# EVB-ANNA-B5_SCHEM_0006_PinHeaders_ULED.net
KiCad netlist of a schematic drawn in Altium Designer
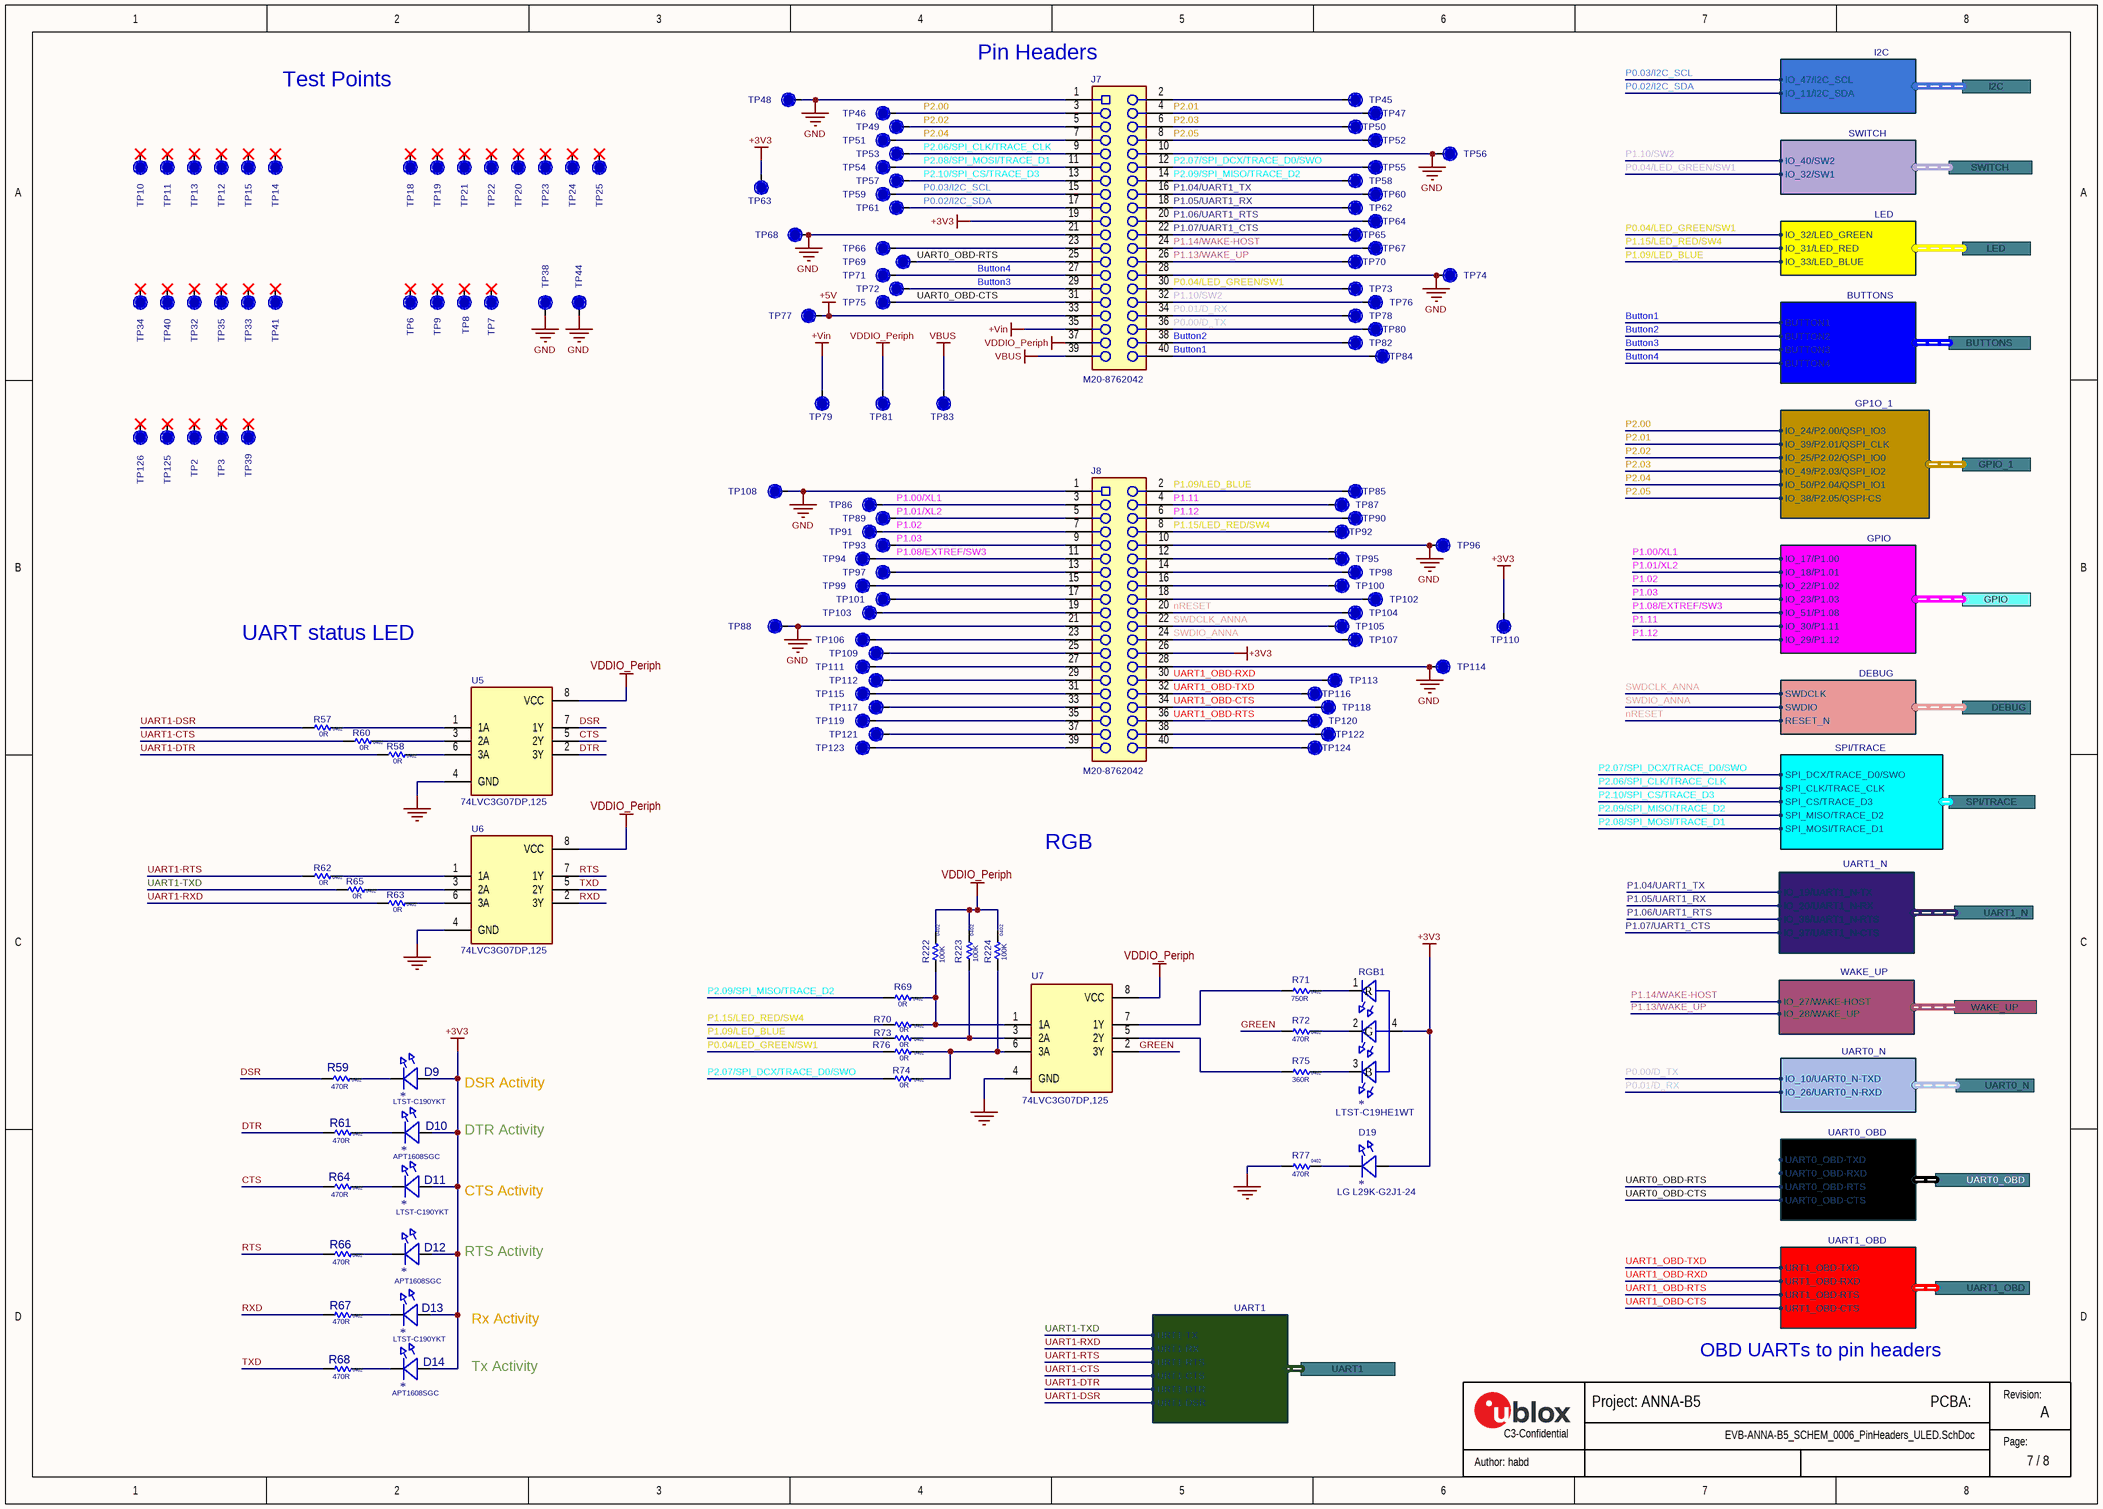
[diagram p0: EVB-ANNA-B5_SCHEM_0006_PinHeaders_ULED.SchDoc]

(export (version "E")
  (design (tool "Eeschema 10.0.6"))
  (components
    (comp (ref "D9")
      (value "UBXH11-0000057")
      (footprint "LED_0603_YELLOW")
      (description "DIODE LED SMT YELLOW CLEAR LENS 2.1V 10MA 0603 YELLOW")
      (fields
        (field (name "COLOR") "*")
        (field (name "MANUFACTURER") "Lite-on Technology Corporation")
        (field (name "MANUFACTURER P/N") "LTST-C190YKT")
        (field (name "EDITOR") "eric.moog")
      )
      (libsource (lib "UBX_Parts_DB_Lib") (part "LED_BASE"))
    )
    (comp (ref "D10")
      (value "UBXH11-0000001")
      (footprint "LED_0603_GREEN")
      (description "LED SMD 0603 GREEN 2.5V 20mA")
      (fields
        (field (name "COLOR") "*")
        (field (name "MANUFACTURER") "Kingbright")
        (field (name "MANUFACTURER P/N") "APT1608SGC")
        (field (name "EDITOR") "gianni.falleroni")
        (field (name "RELEASED BY") "alex.claville")
      )
      (libsource (lib "UBX_Parts_DB_Lib") (part "LED_BASE"))
    )
    (comp (ref "D11")
      (value "UBXH11-0000057")
      (footprint "LED_0603_YELLOW")
      (description "DIODE LED SMT YELLOW CLEAR LENS 2.1V 10MA 0603 YELLOW")
      (fields
        (field (name "COLOR") "*")
        (field (name "MANUFACTURER") "Lite-on Technology Corporation")
        (field (name "MANUFACTURER P/N") "LTST-C190YKT")
        (field (name "EDITOR") "eric.moog")
      )
      (libsource (lib "UBX_Parts_DB_Lib") (part "LED_BASE"))
    )
    (comp (ref "D12")
      (value "UBXH11-0000001")
      (footprint "LED_0603_GREEN")
      (description "LED SMD 0603 GREEN 2.5V 20mA")
      (fields
        (field (name "COLOR") "*")
        (field (name "MANUFACTURER") "Kingbright")
        (field (name "MANUFACTURER P/N") "APT1608SGC")
        (field (name "EDITOR") "gianni.falleroni")
        (field (name "RELEASED BY") "alex.claville")
      )
      (libsource (lib "UBX_Parts_DB_Lib") (part "LED_BASE"))
    )
    (comp (ref "D13")
      (value "UBXH11-0000057")
      (footprint "LED_0603_YELLOW")
      (description "DIODE LED SMT YELLOW CLEAR LENS 2.1V 10MA 0603 YELLOW")
      (fields
        (field (name "COLOR") "*")
        (field (name "MANUFACTURER") "Lite-on Technology Corporation")
        (field (name "MANUFACTURER P/N") "LTST-C190YKT")
        (field (name "EDITOR") "eric.moog")
      )
      (libsource (lib "UBX_Parts_DB_Lib") (part "LED_BASE"))
    )
    (comp (ref "D14")
      (value "UBXH11-0000001")
      (footprint "LED_0603_GREEN")
      (description "LED SMD 0603 GREEN 2.5V 20mA")
      (fields
        (field (name "COLOR") "*")
        (field (name "MANUFACTURER") "Kingbright")
        (field (name "MANUFACTURER P/N") "APT1608SGC")
        (field (name "EDITOR") "gianni.falleroni")
        (field (name "RELEASED BY") "alex.claville")
      )
      (libsource (lib "UBX_Parts_DB_Lib") (part "LED_BASE"))
    )
    (comp (ref "D19")
      (value "UBXH11-0000018")
      (footprint "LED_0603_1600Lx800Wx400H_600x800Pad_800G_FLX")
      (description "LED CHIP 0603 LOW CURRENT OSRAM 0.002A GREEN 2.2V 2mA")
      (fields
        (field (name "COLOR") "*")
        (field (name "MANUFACTURER") "Osram")
        (field (name "MANUFACTURER P/N") "LG L29K-G2J1-24")
        (field (name "EDITOR") "johann.furrer")
        (field (name "RELEASED BY") "martin.grasse")
      )
      (libsource (lib "UBX_Parts_DB_Lib") (part "LED_BASE"))
    )
    (comp (ref "J7")
      (value "~")
      (footprint "M208762042")
      (description "Connector")
      (fields
        (field (name "MANUFACTURER_PART_NUMBER") "M20-8762042")
        (field (name "MOUSER PART NUMBER") "855-M20-8762042")
      )
      (libsource (lib "SamacSys") (part "M20-8762042"))
    )
    (comp (ref "J8")
      (value "~")
      (footprint "M208762042")
      (description "Connector")
      (fields
        (field (name "MANUFACTURER_PART_NUMBER") "M20-8762042")
        (field (name "MOUSER PART NUMBER") "855-M20-8762042")
      )
      (libsource (lib "SamacSys") (part "M20-8762042"))
    )
    (comp (ref "R57")
      (value "0R")
      (footprint "RES 0402 HD")
      (description "RES THICK FILM CHIP 0402 0R 0 100mW")
      (fields
        (field (name "SIZE") "0402")
        (field (name "PART NUMBER") "UBXH18-0003002")
        (field (name "TOLERANCE") "0")
        (field (name "EDITOR") "charlotte.biber")
        (field (name "RELEASED BY") "peter.mueller")
      )
      (libsource (lib "UBX_Parts_DB_Lib") (part "Res sm"))
    )
    (comp (ref "R58")
      (value "0R")
      (footprint "RES 0402 HD")
      (description "RES THICK FILM CHIP 0402 0R 0 100mW")
      (fields
        (field (name "SIZE") "0402")
        (field (name "PART NUMBER") "UBXH18-0003002")
        (field (name "TOLERANCE") "0")
        (field (name "EDITOR") "charlotte.biber")
        (field (name "RELEASED BY") "peter.mueller")
      )
      (libsource (lib "UBX_Parts_DB_Lib") (part "Res sm"))
    )
    (comp (ref "R59")
      (value "470R")
      (footprint "RES_0402_1100Lx600Wx400H_500x600Pad_400G_FLX")
      (description "RES THICK FILM CHIP 0402 470R 5% 100mW")
      (fields
        (field (name "SIZE") "0402")
        (field (name "PART NUMBER") "UBXH18-0008041")
        (field (name "TOLERANCE") "5%")
        (field (name "EDITOR") "roland.rust")
        (field (name "RELEASED BY") "roland.rust")
      )
      (libsource (lib "UBX_Parts_DB_Lib") (part "Res sm"))
    )
    (comp (ref "R60")
      (value "0R")
      (footprint "RES 0402 HD")
      (description "RES THICK FILM CHIP 0402 0R 0 100mW")
      (fields
        (field (name "SIZE") "0402")
        (field (name "PART NUMBER") "UBXH18-0003002")
        (field (name "TOLERANCE") "0")
        (field (name "EDITOR") "charlotte.biber")
        (field (name "RELEASED BY") "peter.mueller")
      )
      (libsource (lib "UBX_Parts_DB_Lib") (part "Res sm"))
    )
    (comp (ref "R61")
      (value "470R")
      (footprint "RES_0402_1100Lx600Wx400H_500x600Pad_400G_FLX")
      (description "RES THICK FILM CHIP 0402 470R 5% 100mW")
      (fields
        (field (name "SIZE") "0402")
        (field (name "PART NUMBER") "UBXH18-0008041")
        (field (name "TOLERANCE") "5%")
        (field (name "EDITOR") "roland.rust")
        (field (name "RELEASED BY") "roland.rust")
      )
      (libsource (lib "UBX_Parts_DB_Lib") (part "Res sm"))
    )
    (comp (ref "R62")
      (value "0R")
      (footprint "RES 0402 HD")
      (description "RES THICK FILM CHIP 0402 0R 0 100mW")
      (fields
        (field (name "SIZE") "0402")
        (field (name "PART NUMBER") "UBXH18-0003002")
        (field (name "TOLERANCE") "0")
        (field (name "EDITOR") "charlotte.biber")
        (field (name "RELEASED BY") "peter.mueller")
      )
      (libsource (lib "UBX_Parts_DB_Lib") (part "Res sm"))
    )
    (comp (ref "R63")
      (value "0R")
      (footprint "RES 0402 HD")
      (description "RES THICK FILM CHIP 0402 0R 0 100mW")
      (fields
        (field (name "SIZE") "0402")
        (field (name "PART NUMBER") "UBXH18-0003002")
        (field (name "TOLERANCE") "0")
        (field (name "EDITOR") "charlotte.biber")
        (field (name "RELEASED BY") "peter.mueller")
      )
      (libsource (lib "UBX_Parts_DB_Lib") (part "Res sm"))
    )
    (comp (ref "R64")
      (value "470R")
      (footprint "RES_0402_1100Lx600Wx400H_500x600Pad_400G_FLX")
      (description "RES THICK FILM CHIP 0402 470R 5% 100mW")
      (fields
        (field (name "SIZE") "0402")
        (field (name "PART NUMBER") "UBXH18-0008041")
        (field (name "TOLERANCE") "5%")
        (field (name "EDITOR") "roland.rust")
        (field (name "RELEASED BY") "roland.rust")
      )
      (libsource (lib "UBX_Parts_DB_Lib") (part "Res sm"))
    )
    (comp (ref "R65")
      (value "0R")
      (footprint "RES 0402 HD")
      (description "RES THICK FILM CHIP 0402 0R 0 100mW")
      (fields
        (field (name "SIZE") "0402")
        (field (name "PART NUMBER") "UBXH18-0003002")
        (field (name "TOLERANCE") "0")
        (field (name "EDITOR") "charlotte.biber")
        (field (name "RELEASED BY") "peter.mueller")
      )
      (libsource (lib "UBX_Parts_DB_Lib") (part "Res sm"))
    )
    (comp (ref "R66")
      (value "470R")
      (footprint "RES_0402_1100Lx600Wx400H_500x600Pad_400G_FLX")
      (description "RES THICK FILM CHIP 0402 470R 5% 100mW")
      (fields
        (field (name "SIZE") "0402")
        (field (name "PART NUMBER") "UBXH18-0008041")
        (field (name "TOLERANCE") "5%")
        (field (name "EDITOR") "roland.rust")
        (field (name "RELEASED BY") "roland.rust")
      )
      (libsource (lib "UBX_Parts_DB_Lib") (part "Res sm"))
    )
    (comp (ref "R67")
      (value "470R")
      (footprint "RES_0402_1100Lx600Wx400H_500x600Pad_400G_FLX")
      (description "RES THICK FILM CHIP 0402 470R 5% 100mW")
      (fields
        (field (name "SIZE") "0402")
        (field (name "PART NUMBER") "UBXH18-0008041")
        (field (name "TOLERANCE") "5%")
        (field (name "EDITOR") "roland.rust")
        (field (name "RELEASED BY") "roland.rust")
      )
      (libsource (lib "UBX_Parts_DB_Lib") (part "Res sm"))
    )
    (comp (ref "R68")
      (value "470R")
      (footprint "RES_0402_1100Lx600Wx400H_500x600Pad_400G_FLX")
      (description "RES THICK FILM CHIP 0402 470R 5% 100mW")
      (fields
        (field (name "SIZE") "0402")
        (field (name "PART NUMBER") "UBXH18-0008041")
        (field (name "TOLERANCE") "5%")
        (field (name "EDITOR") "roland.rust")
        (field (name "RELEASED BY") "roland.rust")
      )
      (libsource (lib "UBX_Parts_DB_Lib") (part "Res sm"))
    )
    (comp (ref "R69")
      (value "0R")
      (footprint "RES 0402 HD")
      (description "RES THICK FILM CHIP 0402 0R 0 100mW")
      (fields
        (field (name "SIZE") "0402")
        (field (name "PART NUMBER") "UBXH18-0003002")
        (field (name "TOLERANCE") "0")
        (field (name "EDITOR") "charlotte.biber")
        (field (name "RELEASED BY") "peter.mueller")
      )
      (libsource (lib "UBX_Parts_DB_Lib") (part "Res sm"))
    )
    (comp (ref "R70")
      (value "0R")
      (footprint "RES 0402 HD")
      (description "RES THICK FILM CHIP 0402 0R 0 100mW")
      (fields
        (field (name "SIZE") "0402")
        (field (name "PART NUMBER") "UBXH18-0003002")
        (field (name "TOLERANCE") "0")
        (field (name "EDITOR") "charlotte.biber")
        (field (name "RELEASED BY") "peter.mueller")
      )
      (libsource (lib "UBX_Parts_DB_Lib") (part "Res sm"))
    )
    (comp (ref "R71")
      (value "750R")
      (footprint "RES_0402_1100Lx600Wx400H_500x600Pad_400G_FLX")
      (description "RES THICK FILM CHIP 0402 750R 5% 100mW")
      (fields
        (field (name "SIZE") "0402")
        (field (name "PART NUMBER") "UBXH18-0008046")
        (field (name "TOLERANCE") "5%")
        (field (name "EDITOR") "jaka.bevk")
        (field (name "RELEASED BY") "erian.bezhani")
      )
      (libsource (lib "UBX_Parts_DB_Lib") (part "Res sm"))
    )
    (comp (ref "R72")
      (value "470R")
      (footprint "RES_0402_1100Lx600Wx400H_500x600Pad_400G_FLX")
      (description "RES THICK FILM CHIP 0402 470R 5% 100mW")
      (fields
        (field (name "SIZE") "0402")
        (field (name "PART NUMBER") "UBXH18-0008041")
        (field (name "TOLERANCE") "5%")
        (field (name "EDITOR") "roland.rust")
        (field (name "RELEASED BY") "roland.rust")
      )
      (libsource (lib "UBX_Parts_DB_Lib") (part "Res sm"))
    )
    (comp (ref "R73")
      (value "0R")
      (footprint "RES 0402 HD")
      (description "RES THICK FILM CHIP 0402 0R 0 100mW")
      (fields
        (field (name "SIZE") "0402")
        (field (name "PART NUMBER") "UBXH18-0003002")
        (field (name "TOLERANCE") "0")
        (field (name "EDITOR") "charlotte.biber")
        (field (name "RELEASED BY") "peter.mueller")
      )
      (libsource (lib "UBX_Parts_DB_Lib") (part "Res sm"))
    )
    (comp (ref "R74")
      (value "0R")
      (footprint "RES 0402 HD")
      (description "RES THICK FILM CHIP 0402 0R 0 100mW")
      (fields
        (field (name "SIZE") "0402")
        (field (name "PART NUMBER") "UBXH18-0003002")
        (field (name "TOLERANCE") "0")
        (field (name "EDITOR") "charlotte.biber")
        (field (name "RELEASED BY") "peter.mueller")
      )
      (libsource (lib "UBX_Parts_DB_Lib") (part "Res sm"))
    )
    (comp (ref "R75")
      (value "360R")
      (footprint "RES_0402_1100Lx600Wx400H_500x600Pad_400G_FLX")
      (description "RES THICK FILM CHIP 0402 360R 1% 63mW")
      (fields
        (field (name "SIZE") "0402")
        (field (name "PART NUMBER") "UBXH18-0000216")
        (field (name "TOLERANCE") "1%")
        (field (name "EDITOR") "michael.hein")
        (field (name "RELEASED BY") "vasyl.dykyy")
      )
      (libsource (lib "UBX_Parts_DB_Lib") (part "Res sm"))
    )
    (comp (ref "R76")
      (value "0R")
      (footprint "RES 0402 HD")
      (description "RES THICK FILM CHIP 0402 0R 0 100mW")
      (fields
        (field (name "SIZE") "0402")
        (field (name "PART NUMBER") "UBXH18-0003002")
        (field (name "TOLERANCE") "0")
        (field (name "EDITOR") "charlotte.biber")
        (field (name "RELEASED BY") "peter.mueller")
      )
      (libsource (lib "UBX_Parts_DB_Lib") (part "Res sm"))
    )
    (comp (ref "R77")
      (value "470R")
      (footprint "RES_0402_1100Lx600Wx400H_500x600Pad_400G_FLX")
      (description "RES THICK FILM CHIP 0402 470R 5% 100mW")
      (fields
        (field (name "SIZE") "0402")
        (field (name "PART NUMBER") "UBXH18-0008041")
        (field (name "TOLERANCE") "5%")
        (field (name "EDITOR") "roland.rust")
        (field (name "RELEASED BY") "roland.rust")
      )
      (libsource (lib "UBX_Parts_DB_Lib") (part "Res sm"))
    )
    (comp (ref "R222")
      (value "100K")
      (footprint "RES 0402 HD")
      (description "RES THICK FILM CHIP 0402 100K 1% 63mW")
      (fields
        (field (name "SIZE") "0402")
        (field (name "PART NUMBER") "UBXH18-0000005")
        (field (name "TOLERANCE") "1%")
        (field (name "EDITOR") "dario.antonaz")
        (field (name "RELEASED BY") "sandro.sestan")
      )
      (libsource (lib "UBX_Parts_DB_Lib") (part "Res sm"))
    )
    (comp (ref "R223")
      (value "100K")
      (footprint "RES 0402 HD")
      (description "RES THICK FILM CHIP 0402 100K 1% 63mW")
      (fields
        (field (name "SIZE") "0402")
        (field (name "PART NUMBER") "UBXH18-0000005")
        (field (name "TOLERANCE") "1%")
        (field (name "EDITOR") "dario.antonaz")
        (field (name "RELEASED BY") "sandro.sestan")
      )
      (libsource (lib "UBX_Parts_DB_Lib") (part "Res sm"))
    )
    (comp (ref "R224")
      (value "100K")
      (footprint "RES 0402 HD")
      (description "RES THICK FILM CHIP 0402 100K 1% 63mW")
      (fields
        (field (name "SIZE") "0402")
        (field (name "PART NUMBER") "UBXH18-0000005")
        (field (name "TOLERANCE") "1%")
        (field (name "EDITOR") "dario.antonaz")
        (field (name "RELEASED BY") "sandro.sestan")
      )
      (libsource (lib "UBX_Parts_DB_Lib") (part "Res sm"))
    )
    (comp (ref "RGB1")
      (value "115-00026")
      (footprint "LED_1616")
      (description "LED RGB SMT 0606")
      (fields
        (field (name "COLOR") "*")
        (field (name "MANUFACTURER PART NUMBER 1") "LTST-C19HE1WT")
        (field (name "VOLTAGE") "None")
      )
      (libsource (lib "Arena_Parts_DB_Lib") (part "LED_RGB_CA_4"))
    )
    (comp (ref "TP2")
      (value "TP10R")
      (footprint "TP10R")
      (description "Testpoint, Round 1.0mm Dia")
      (fields (field (name "ADDED BY") "Jeremy D") (field (name "CHECKED BY") "Paul B"))
      (libsource (lib "LEGACY_Rigado_AltiumLib") (part "TP_R"))
    )
    (comp (ref "TP3")
      (value "TP10R")
      (footprint "TP10R")
      (description "Testpoint, Round 1.0mm Dia")
      (fields (field (name "ADDED BY") "Jeremy D") (field (name "CHECKED BY") "Paul B"))
      (libsource (lib "LEGACY_Rigado_AltiumLib") (part "TP_R"))
    )
    (comp (ref "TP6")
      (value "TP10R")
      (footprint "TP10R")
      (description "Testpoint, Round 1.0mm Dia")
      (fields (field (name "ADDED BY") "Jeremy D") (field (name "CHECKED BY") "Paul B"))
      (libsource (lib "") (part "TP_R_1"))
    )
    (comp (ref "TP7")
      (value "TP10R")
      (footprint "TP10R")
      (description "Testpoint, Round 1.0mm Dia")
      (fields (field (name "ADDED BY") "Jeremy D") (field (name "CHECKED BY") "Paul B"))
      (libsource (lib "LEGACY_Rigado_AltiumLib") (part "TP_R"))
    )
    (comp (ref "TP8")
      (value "TP10R")
      (footprint "TP10R")
      (description "Testpoint, Round 1.0mm Dia")
      (fields (field (name "ADDED BY") "Jeremy D") (field (name "CHECKED BY") "Paul B"))
      (libsource (lib "LEGACY_Rigado_AltiumLib") (part "TP_R"))
    )
    (comp (ref "TP9")
      (value "TP10R")
      (footprint "TP10R")
      (description "Testpoint, Round 1.0mm Dia")
      (fields (field (name "ADDED BY") "Jeremy D") (field (name "CHECKED BY") "Paul B"))
      (libsource (lib "LEGACY_Rigado_AltiumLib") (part "TP_R"))
    )
    (comp (ref "TP10")
      (value "TP10R")
      (footprint "TP10R")
      (description "Testpoint, Round 1.0mm Dia")
      (fields (field (name "ADDED BY") "Jeremy D") (field (name "CHECKED BY") "Paul B"))
      (libsource (lib "LEGACY_Rigado_AltiumLib") (part "TP_R"))
    )
    (comp (ref "TP11")
      (value "TP10R")
      (footprint "TP10R")
      (description "Testpoint, Round 1.0mm Dia")
      (fields (field (name "ADDED BY") "Jeremy D") (field (name "CHECKED BY") "Paul B"))
      (libsource (lib "LEGACY_Rigado_AltiumLib") (part "TP_R"))
    )
    (comp (ref "TP12")
      (value "TP10R")
      (footprint "TP10R")
      (description "Testpoint, Round 1.0mm Dia")
      (fields (field (name "ADDED BY") "Jeremy D") (field (name "CHECKED BY") "Paul B"))
      (libsource (lib "LEGACY_Rigado_AltiumLib") (part "TP_R"))
    )
    (comp (ref "TP13")
      (value "TP10R")
      (footprint "TP10R")
      (description "Testpoint, Round 1.0mm Dia")
      (fields (field (name "ADDED BY") "Jeremy D") (field (name "CHECKED BY") "Paul B"))
      (libsource (lib "LEGACY_Rigado_AltiumLib") (part "TP_R"))
    )
    (comp (ref "TP14")
      (value "TP10R")
      (footprint "TP10R")
      (description "Testpoint, Round 1.0mm Dia")
      (fields (field (name "ADDED BY") "Jeremy D") (field (name "CHECKED BY") "Paul B"))
      (libsource (lib "LEGACY_Rigado_AltiumLib") (part "TP_R"))
    )
    (comp (ref "TP15")
      (value "TP10R")
      (footprint "TP10R")
      (description "Testpoint, Round 1.0mm Dia")
      (fields (field (name "ADDED BY") "Jeremy D") (field (name "CHECKED BY") "Paul B"))
      (libsource (lib "LEGACY_Rigado_AltiumLib") (part "TP_R"))
    )
    (comp (ref "TP18")
      (value "TP10R")
      (footprint "TP10R")
      (description "Testpoint, Round 1.0mm Dia")
      (fields (field (name "ADDED BY") "Jeremy D") (field (name "CHECKED BY") "Paul B"))
      (libsource (lib "LEGACY_Rigado_AltiumLib") (part "TP_R"))
    )
    (comp (ref "TP19")
      (value "TP10R")
      (footprint "TP10R")
      (description "Testpoint, Round 1.0mm Dia")
      (fields (field (name "ADDED BY") "Jeremy D") (field (name "CHECKED BY") "Paul B"))
      (libsource (lib "LEGACY_Rigado_AltiumLib") (part "TP_R"))
    )
    (comp (ref "TP20")
      (value "TP10R")
      (footprint "TP10R")
      (description "Testpoint, Round 1.0mm Dia")
      (fields (field (name "ADDED BY") "Jeremy D") (field (name "CHECKED BY") "Paul B"))
      (libsource (lib "LEGACY_Rigado_AltiumLib") (part "TP_R"))
    )
    (comp (ref "TP21")
      (value "TP10R")
      (footprint "TP10R")
      (description "Testpoint, Round 1.0mm Dia")
      (fields (field (name "ADDED BY") "Jeremy D") (field (name "CHECKED BY") "Paul B"))
      (libsource (lib "LEGACY_Rigado_AltiumLib") (part "TP_R"))
    )
    (comp (ref "TP22")
      (value "TP10R")
      (footprint "TP10R")
      (description "Testpoint, Round 1.0mm Dia")
      (fields (field (name "ADDED BY") "Jeremy D") (field (name "CHECKED BY") "Paul B"))
      (libsource (lib "LEGACY_Rigado_AltiumLib") (part "TP_R"))
    )
    (comp (ref "TP23")
      (value "TP10R")
      (footprint "TP10R")
      (description "Testpoint, Round 1.0mm Dia")
      (fields (field (name "ADDED BY") "Jeremy D") (field (name "CHECKED BY") "Paul B"))
      (libsource (lib "LEGACY_Rigado_AltiumLib") (part "TP_R"))
    )
    (comp (ref "TP24")
      (value "TP10R")
      (footprint "TP10R")
      (description "Testpoint, Round 1.0mm Dia")
      (fields (field (name "ADDED BY") "Jeremy D") (field (name "CHECKED BY") "Paul B"))
      (libsource (lib "LEGACY_Rigado_AltiumLib") (part "TP_R"))
    )
    (comp (ref "TP25")
      (value "TP10R")
      (footprint "TP10R")
      (description "Testpoint, Round 1.0mm Dia")
      (fields (field (name "ADDED BY") "Jeremy D") (field (name "CHECKED BY") "Paul B"))
      (libsource (lib "LEGACY_Rigado_AltiumLib") (part "TP_R"))
    )
    (comp (ref "TP32")
      (value "TP10R")
      (footprint "TP10R")
      (description "Testpoint, Round 1.0mm Dia")
      (fields (field (name "ADDED BY") "Jeremy D") (field (name "CHECKED BY") "Paul B"))
      (libsource (lib "LEGACY_Rigado_AltiumLib") (part "TP_R"))
    )
    (comp (ref "TP33")
      (value "TP10R")
      (footprint "TP10R")
      (description "Testpoint, Round 1.0mm Dia")
      (fields (field (name "ADDED BY") "Jeremy D") (field (name "CHECKED BY") "Paul B"))
      (libsource (lib "LEGACY_Rigado_AltiumLib") (part "TP_R"))
    )
    (comp (ref "TP34")
      (value "TP10R")
      (footprint "TP10R")
      (description "Testpoint, Round 1.0mm Dia")
      (fields (field (name "ADDED BY") "Jeremy D") (field (name "CHECKED BY") "Paul B"))
      (libsource (lib "LEGACY_Rigado_AltiumLib") (part "TP_R"))
    )
    (comp (ref "TP35")
      (value "TP10R")
      (footprint "TP10R")
      (description "Testpoint, Round 1.0mm Dia")
      (fields (field (name "ADDED BY") "Jeremy D") (field (name "CHECKED BY") "Paul B"))
      (libsource (lib "LEGACY_Rigado_AltiumLib") (part "TP_R"))
    )
    (comp (ref "TP38")
      (value "TP10R")
      (footprint "TP10R")
      (description "Testpoint, Round 1.0mm Dia")
      (fields (field (name "ADDED BY") "Jeremy D") (field (name "CHECKED BY") "Paul B"))
      (libsource (lib "LEGACY_Rigado_AltiumLib") (part "TP_R"))
    )
    (comp (ref "TP39")
      (value "TP10R")
      (footprint "TP10R")
      (description "Testpoint, Round 1.0mm Dia")
      (fields (field (name "ADDED BY") "Jeremy D") (field (name "CHECKED BY") "Paul B"))
      (libsource (lib "LEGACY_Rigado_AltiumLib") (part "TP_R"))
    )
    (comp (ref "TP40")
      (value "TP10R")
      (footprint "TP10R")
      (description "Testpoint, Round 1.0mm Dia")
      (fields (field (name "ADDED BY") "Jeremy D") (field (name "CHECKED BY") "Paul B"))
      (libsource (lib "LEGACY_Rigado_AltiumLib") (part "TP_R"))
    )
    (comp (ref "TP41")
      (value "TP10R")
      (footprint "TP10R")
      (description "Testpoint, Round 1.0mm Dia")
      (fields (field (name "ADDED BY") "Jeremy D") (field (name "CHECKED BY") "Paul B"))
      (libsource (lib "LEGACY_Rigado_AltiumLib") (part "TP_R"))
    )
    (comp (ref "TP44")
      (value "TP10R")
      (footprint "TP10R")
      (description "Testpoint, Round 1.0mm Dia")
      (fields (field (name "ADDED BY") "Jeremy D") (field (name "CHECKED BY") "Paul B"))
      (libsource (lib "LEGACY_Rigado_AltiumLib") (part "TP_R"))
    )
    (comp (ref "TP45")
      (value "TP10R")
      (footprint "TP10R")
      (description "Testpoint, Round 1.0mm Dia")
      (fields (field (name "ADDED BY") "Jeremy D") (field (name "CHECKED BY") "Paul B"))
      (libsource (lib "LEGACY_Rigado_AltiumLib") (part "TP_R"))
    )
    (comp (ref "TP46")
      (value "TP10R")
      (footprint "TP10R")
      (description "Testpoint, Round 1.0mm Dia")
      (fields (field (name "ADDED BY") "Jeremy D") (field (name "CHECKED BY") "Paul B"))
      (libsource (lib "LEGACY_Rigado_AltiumLib") (part "TP_R"))
    )
    (comp (ref "TP47")
      (value "TP10R")
      (footprint "TP10R")
      (description "Testpoint, Round 1.0mm Dia")
      (fields (field (name "ADDED BY") "Jeremy D") (field (name "CHECKED BY") "Paul B"))
      (libsource (lib "") (part "TP_R_1"))
    )
    (comp (ref "TP48")
      (value "TP10R")
      (footprint "TP10R")
      (description "Testpoint, Round 1.0mm Dia")
      (fields (field (name "ADDED BY") "Jeremy D") (field (name "CHECKED BY") "Paul B"))
      (libsource (lib "LEGACY_Rigado_AltiumLib") (part "TP_R"))
    )
    (comp (ref "TP49")
      (value "TP10R")
      (footprint "TP10R")
      (description "Testpoint, Round 1.0mm Dia")
      (fields (field (name "ADDED BY") "Jeremy D") (field (name "CHECKED BY") "Paul B"))
      (libsource (lib "LEGACY_Rigado_AltiumLib") (part "TP_R"))
    )
    (comp (ref "TP50")
      (value "TP10R")
      (footprint "TP10R")
      (description "Testpoint, Round 1.0mm Dia")
      (fields (field (name "ADDED BY") "Jeremy D") (field (name "CHECKED BY") "Paul B"))
      (libsource (lib "") (part "TP_R_1"))
    )
    (comp (ref "TP51")
      (value "TP10R")
      (footprint "TP10R")
      (description "Testpoint, Round 1.0mm Dia")
      (fields (field (name "ADDED BY") "Jeremy D") (field (name "CHECKED BY") "Paul B"))
      (libsource (lib "LEGACY_Rigado_AltiumLib") (part "TP_R"))
    )
    (comp (ref "TP52")
      (value "TP10R")
      (footprint "TP10R")
      (description "Testpoint, Round 1.0mm Dia")
      (fields (field (name "ADDED BY") "Jeremy D") (field (name "CHECKED BY") "Paul B"))
      (libsource (lib "LEGACY_Rigado_AltiumLib") (part "TP_R"))
    )
    (comp (ref "TP53")
      (value "TP10R")
      (footprint "TP10R")
      (description "Testpoint, Round 1.0mm Dia")
      (fields (field (name "ADDED BY") "Jeremy D") (field (name "CHECKED BY") "Paul B"))
      (libsource (lib "LEGACY_Rigado_AltiumLib") (part "TP_R"))
    )
    (comp (ref "TP54")
      (value "TP10R")
      (footprint "TP10R")
      (description "Testpoint, Round 1.0mm Dia")
      (fields (field (name "ADDED BY") "Jeremy D") (field (name "CHECKED BY") "Paul B"))
      (libsource (lib "LEGACY_Rigado_AltiumLib") (part "TP_R"))
    )
    (comp (ref "TP55")
      (value "TP10R")
      (footprint "TP10R")
      (description "Testpoint, Round 1.0mm Dia")
      (fields (field (name "ADDED BY") "Jeremy D") (field (name "CHECKED BY") "Paul B"))
      (libsource (lib "LEGACY_Rigado_AltiumLib") (part "TP_R"))
    )
    (comp (ref "TP56")
      (value "TP10R")
      (footprint "TP10R")
      (description "Testpoint, Round 1.0mm Dia")
      (fields (field (name "ADDED BY") "Jeremy D") (field (name "CHECKED BY") "Paul B"))
      (libsource (lib "LEGACY_Rigado_AltiumLib") (part "TP_R"))
    )
    (comp (ref "TP57")
      (value "TP10R")
      (footprint "TP10R")
      (description "Testpoint, Round 1.0mm Dia")
      (fields (field (name "ADDED BY") "Jeremy D") (field (name "CHECKED BY") "Paul B"))
      (libsource (lib "LEGACY_Rigado_AltiumLib") (part "TP_R"))
    )
    (comp (ref "TP58")
      (value "TP10R")
      (footprint "TP10R")
      (description "Testpoint, Round 1.0mm Dia")
      (fields (field (name "ADDED BY") "Jeremy D") (field (name "CHECKED BY") "Paul B"))
      (libsource (lib "LEGACY_Rigado_AltiumLib") (part "TP_R"))
    )
    (comp (ref "TP59")
      (value "TP10R")
      (footprint "TP10R")
      (description "Testpoint, Round 1.0mm Dia")
      (fields (field (name "ADDED BY") "Jeremy D") (field (name "CHECKED BY") "Paul B"))
      (libsource (lib "LEGACY_Rigado_AltiumLib") (part "TP_R"))
    )
    (comp (ref "TP60")
      (value "TP10R")
      (footprint "TP10R")
      (description "Testpoint, Round 1.0mm Dia")
      (fields (field (name "ADDED BY") "Jeremy D") (field (name "CHECKED BY") "Paul B"))
      (libsource (lib "LEGACY_Rigado_AltiumLib") (part "TP_R"))
    )
    (comp (ref "TP61")
      (value "TP10R")
      (footprint "TP10R")
      (description "Testpoint, Round 1.0mm Dia")
      (fields (field (name "ADDED BY") "Jeremy D") (field (name "CHECKED BY") "Paul B"))
      (libsource (lib "LEGACY_Rigado_AltiumLib") (part "TP_R"))
    )
    (comp (ref "TP62")
      (value "TP10R")
      (footprint "TP10R")
      (description "Testpoint, Round 1.0mm Dia")
      (fields (field (name "ADDED BY") "Jeremy D") (field (name "CHECKED BY") "Paul B"))
      (libsource (lib "LEGACY_Rigado_AltiumLib") (part "TP_R"))
    )
    (comp (ref "TP63")
      (value "TP10R")
      (footprint "TP10R")
      (description "Testpoint, Round 1.0mm Dia")
      (fields (field (name "ADDED BY") "Jeremy D") (field (name "CHECKED BY") "Paul B"))
      (libsource (lib "LEGACY_Rigado_AltiumLib") (part "TP_R"))
    )
    (comp (ref "TP64")
      (value "TP10R")
      (footprint "TP10R")
      (description "Testpoint, Round 1.0mm Dia")
      (fields (field (name "ADDED BY") "Jeremy D") (field (name "CHECKED BY") "Paul B"))
      (libsource (lib "") (part "TP_R_1"))
    )
    (comp (ref "TP65")
      (value "TP10R")
      (footprint "TP10R")
      (description "Testpoint, Round 1.0mm Dia")
      (fields (field (name "ADDED BY") "Jeremy D") (field (name "CHECKED BY") "Paul B"))
      (libsource (lib "") (part "TP_R_1"))
    )
    (comp (ref "TP66")
      (value "TP10R")
      (footprint "TP10R")
      (description "Testpoint, Round 1.0mm Dia")
      (fields (field (name "ADDED BY") "Jeremy D") (field (name "CHECKED BY") "Paul B"))
      (libsource (lib "LEGACY_Rigado_AltiumLib") (part "TP_R"))
    )
    (comp (ref "TP67")
      (value "TP10R")
      (footprint "TP10R")
      (description "Testpoint, Round 1.0mm Dia")
      (fields (field (name "ADDED BY") "Jeremy D") (field (name "CHECKED BY") "Paul B"))
      (libsource (lib "") (part "TP_R_1"))
    )
    (comp (ref "TP68")
      (value "TP10R")
      (footprint "TP10R")
      (description "Testpoint, Round 1.0mm Dia")
      (fields (field (name "ADDED BY") "Jeremy D") (field (name "CHECKED BY") "Paul B"))
      (libsource (lib "LEGACY_Rigado_AltiumLib") (part "TP_R"))
    )
    (comp (ref "TP69")
      (value "TP10R")
      (footprint "TP10R")
      (description "Testpoint, Round 1.0mm Dia")
      (fields (field (name "ADDED BY") "Jeremy D") (field (name "CHECKED BY") "Paul B"))
      (libsource (lib "LEGACY_Rigado_AltiumLib") (part "TP_R"))
    )
    (comp (ref "TP70")
      (value "TP10R")
      (footprint "TP10R")
      (description "Testpoint, Round 1.0mm Dia")
      (fields (field (name "ADDED BY") "Jeremy D") (field (name "CHECKED BY") "Paul B"))
      (libsource (lib "LEGACY_Rigado_AltiumLib") (part "TP_R"))
    )
    (comp (ref "TP71")
      (value "TP10R")
      (footprint "TP10R")
      (description "Testpoint, Round 1.0mm Dia")
      (fields (field (name "ADDED BY") "Jeremy D") (field (name "CHECKED BY") "Paul B"))
      (libsource (lib "LEGACY_Rigado_AltiumLib") (part "TP_R"))
    )
    (comp (ref "TP72")
      (value "TP10R")
      (footprint "TP10R")
      (description "Testpoint, Round 1.0mm Dia")
      (fields (field (name "ADDED BY") "Jeremy D") (field (name "CHECKED BY") "Paul B"))
      (libsource (lib "LEGACY_Rigado_AltiumLib") (part "TP_R"))
    )
    (comp (ref "TP73")
      (value "TP10R")
      (footprint "TP10R")
      (description "Testpoint, Round 1.0mm Dia")
      (fields (field (name "ADDED BY") "Jeremy D") (field (name "CHECKED BY") "Paul B"))
      (libsource (lib "") (part "TP_R_1"))
    )
    (comp (ref "TP74")
      (value "TP10R")
      (footprint "TP10R")
      (description "Testpoint, Round 1.0mm Dia")
      (fields (field (name "ADDED BY") "Jeremy D") (field (name "CHECKED BY") "Paul B"))
      (libsource (lib "") (part "TP_R_1"))
    )
    (comp (ref "TP75")
      (value "TP10R")
      (footprint "TP10R")
      (description "Testpoint, Round 1.0mm Dia")
      (fields (field (name "ADDED BY") "Jeremy D") (field (name "CHECKED BY") "Paul B"))
      (libsource (lib "LEGACY_Rigado_AltiumLib") (part "TP_R"))
    )
    (comp (ref "TP76")
      (value "TP10R")
      (footprint "TP10R")
      (description "Testpoint, Round 1.0mm Dia")
      (fields (field (name "ADDED BY") "Jeremy D") (field (name "CHECKED BY") "Paul B"))
      (libsource (lib "") (part "TP_R_1"))
    )
    (comp (ref "TP77")
      (value "TP10R")
      (footprint "TP10R")
      (description "Testpoint, Round 1.0mm Dia")
      (fields (field (name "ADDED BY") "Jeremy D") (field (name "CHECKED BY") "Paul B"))
      (libsource (lib "LEGACY_Rigado_AltiumLib") (part "TP_R"))
    )
    (comp (ref "TP78")
      (value "TP10R")
      (footprint "TP10R")
      (description "Testpoint, Round 1.0mm Dia")
      (fields (field (name "ADDED BY") "Jeremy D") (field (name "CHECKED BY") "Paul B"))
      (libsource (lib "") (part "TP_R_1"))
    )
    (comp (ref "TP79")
      (value "TP10R")
      (footprint "TP10R")
      (description "Testpoint, Round 1.0mm Dia")
      (fields (field (name "ADDED BY") "Jeremy D") (field (name "CHECKED BY") "Paul B"))
      (libsource (lib "LEGACY_Rigado_AltiumLib") (part "TP_R"))
    )
    (comp (ref "TP80")
      (value "TP10R")
      (footprint "TP10R")
      (description "Testpoint, Round 1.0mm Dia")
      (fields (field (name "ADDED BY") "Jeremy D") (field (name "CHECKED BY") "Paul B"))
      (libsource (lib "") (part "TP_R_1"))
    )
    (comp (ref "TP81")
      (value "TP10R")
      (footprint "TP10R")
      (description "Testpoint, Round 1.0mm Dia")
      (fields (field (name "ADDED BY") "Jeremy D") (field (name "CHECKED BY") "Paul B"))
      (libsource (lib "LEGACY_Rigado_AltiumLib") (part "TP_R"))
    )
    (comp (ref "TP82")
      (value "TP10R")
      (footprint "TP10R")
      (description "Testpoint, Round 1.0mm Dia")
      (fields (field (name "ADDED BY") "Jeremy D") (field (name "CHECKED BY") "Paul B"))
      (libsource (lib "") (part "TP_R_1"))
    )
    (comp (ref "TP83")
      (value "TP10R")
      (footprint "TP10R")
      (description "Testpoint, Round 1.0mm Dia")
      (fields (field (name "ADDED BY") "Jeremy D") (field (name "CHECKED BY") "Paul B"))
      (libsource (lib "LEGACY_Rigado_AltiumLib") (part "TP_R"))
    )
    (comp (ref "TP84")
      (value "TP10R")
      (footprint "TP10R")
      (description "Testpoint, Round 1.0mm Dia")
      (fields (field (name "ADDED BY") "Jeremy D") (field (name "CHECKED BY") "Paul B"))
      (libsource (lib "") (part "TP_R_1"))
    )
    (comp (ref "TP85")
      (value "TP10R")
      (footprint "TP10R")
      (description "Testpoint, Round 1.0mm Dia")
      (fields (field (name "ADDED BY") "Jeremy D") (field (name "CHECKED BY") "Paul B"))
      (libsource (lib "") (part "TP_R_1"))
    )
    (comp (ref "TP86")
      (value "TP10R")
      (footprint "TP10R")
      (description "Testpoint, Round 1.0mm Dia")
      (fields (field (name "ADDED BY") "Jeremy D") (field (name "CHECKED BY") "Paul B"))
      (libsource (lib "LEGACY_Rigado_AltiumLib") (part "TP_R"))
    )
    (comp (ref "TP87")
      (value "TP10R")
      (footprint "TP10R")
      (description "Testpoint, Round 1.0mm Dia")
      (fields (field (name "ADDED BY") "Jeremy D") (field (name "CHECKED BY") "Paul B"))
      (libsource (lib "") (part "TP_R_1"))
    )
    (comp (ref "TP88")
      (value "TP10R")
      (footprint "TP10R")
      (description "Testpoint, Round 1.0mm Dia")
      (fields (field (name "ADDED BY") "Jeremy D") (field (name "CHECKED BY") "Paul B"))
      (libsource (lib "LEGACY_Rigado_AltiumLib") (part "TP_R"))
    )
    (comp (ref "TP89")
      (value "TP10R")
      (footprint "TP10R")
      (description "Testpoint, Round 1.0mm Dia")
      (fields (field (name "ADDED BY") "Jeremy D") (field (name "CHECKED BY") "Paul B"))
      (libsource (lib "LEGACY_Rigado_AltiumLib") (part "TP_R"))
    )
    (comp (ref "TP90")
      (value "TP10R")
      (footprint "TP10R")
      (description "Testpoint, Round 1.0mm Dia")
      (fields (field (name "ADDED BY") "Jeremy D") (field (name "CHECKED BY") "Paul B"))
      (libsource (lib "") (part "TP_R_1"))
    )
    (comp (ref "TP91")
      (value "TP10R")
      (footprint "TP10R")
      (description "Testpoint, Round 1.0mm Dia")
      (fields (field (name "ADDED BY") "Jeremy D") (field (name "CHECKED BY") "Paul B"))
      (libsource (lib "LEGACY_Rigado_AltiumLib") (part "TP_R"))
    )
    (comp (ref "TP92")
      (value "TP10R")
      (footprint "TP10R")
      (description "Testpoint, Round 1.0mm Dia")
      (fields (field (name "ADDED BY") "Jeremy D") (field (name "CHECKED BY") "Paul B"))
      (libsource (lib "LEGACY_Rigado_AltiumLib") (part "TP_R"))
    )
    (comp (ref "TP93")
      (value "TP10R")
      (footprint "TP10R")
      (description "Testpoint, Round 1.0mm Dia")
      (fields (field (name "ADDED BY") "Jeremy D") (field (name "CHECKED BY") "Paul B"))
      (libsource (lib "LEGACY_Rigado_AltiumLib") (part "TP_R"))
    )
    (comp (ref "TP94")
      (value "TP10R")
      (footprint "TP10R")
      (description "Testpoint, Round 1.0mm Dia")
      (fields (field (name "ADDED BY") "Jeremy D") (field (name "CHECKED BY") "Paul B"))
      (libsource (lib "LEGACY_Rigado_AltiumLib") (part "TP_R"))
    )
    (comp (ref "TP95")
      (value "TP10R")
      (footprint "TP10R")
      (description "Testpoint, Round 1.0mm Dia")
      (fields (field (name "ADDED BY") "Jeremy D") (field (name "CHECKED BY") "Paul B"))
      (libsource (lib "LEGACY_Rigado_AltiumLib") (part "TP_R"))
    )
    (comp (ref "TP96")
      (value "TP10R")
      (footprint "TP10R")
      (description "Testpoint, Round 1.0mm Dia")
      (fields (field (name "ADDED BY") "Jeremy D") (field (name "CHECKED BY") "Paul B"))
      (libsource (lib "") (part "TP_R_1"))
    )
    (comp (ref "TP97")
      (value "TP10R")
      (footprint "TP10R")
      (description "Testpoint, Round 1.0mm Dia")
      (fields (field (name "ADDED BY") "Jeremy D") (field (name "CHECKED BY") "Paul B"))
      (libsource (lib "LEGACY_Rigado_AltiumLib") (part "TP_R"))
    )
    (comp (ref "TP98")
      (value "TP10R")
      (footprint "TP10R")
      (description "Testpoint, Round 1.0mm Dia")
      (fields (field (name "ADDED BY") "Jeremy D") (field (name "CHECKED BY") "Paul B"))
      (libsource (lib "LEGACY_Rigado_AltiumLib") (part "TP_R"))
    )
    (comp (ref "TP99")
      (value "TP10R")
      (footprint "TP10R")
      (description "Testpoint, Round 1.0mm Dia")
      (fields (field (name "ADDED BY") "Jeremy D") (field (name "CHECKED BY") "Paul B"))
      (libsource (lib "LEGACY_Rigado_AltiumLib") (part "TP_R"))
    )
    (comp (ref "TP100")
      (value "TP10R")
      (footprint "TP10R")
      (description "Testpoint, Round 1.0mm Dia")
      (fields (field (name "ADDED BY") "Jeremy D") (field (name "CHECKED BY") "Paul B"))
      (libsource (lib "LEGACY_Rigado_AltiumLib") (part "TP_R"))
    )
    (comp (ref "TP101")
      (value "TP10R")
      (footprint "TP10R")
      (description "Testpoint, Round 1.0mm Dia")
      (fields (field (name "ADDED BY") "Jeremy D") (field (name "CHECKED BY") "Paul B"))
      (libsource (lib "LEGACY_Rigado_AltiumLib") (part "TP_R"))
    )
    (comp (ref "TP102")
      (value "TP10R")
      (footprint "TP10R")
      (description "Testpoint, Round 1.0mm Dia")
      (fields (field (name "ADDED BY") "Jeremy D") (field (name "CHECKED BY") "Paul B"))
      (libsource (lib "LEGACY_Rigado_AltiumLib") (part "TP_R"))
    )
    (comp (ref "TP103")
      (value "TP10R")
      (footprint "TP10R")
      (description "Testpoint, Round 1.0mm Dia")
      (fields (field (name "ADDED BY") "Jeremy D") (field (name "CHECKED BY") "Paul B"))
      (libsource (lib "LEGACY_Rigado_AltiumLib") (part "TP_R"))
    )
    (comp (ref "TP104")
      (value "TP10R")
      (footprint "TP10R")
      (description "Testpoint, Round 1.0mm Dia")
      (fields (field (name "ADDED BY") "Jeremy D") (field (name "CHECKED BY") "Paul B"))
      (libsource (lib "LEGACY_Rigado_AltiumLib") (part "TP_R"))
    )
    (comp (ref "TP105")
      (value "TP10R")
      (footprint "TP10R")
      (description "Testpoint, Round 1.0mm Dia")
      (fields (field (name "ADDED BY") "Jeremy D") (field (name "CHECKED BY") "Paul B"))
      (libsource (lib "LEGACY_Rigado_AltiumLib") (part "TP_R"))
    )
    (comp (ref "TP106")
      (value "TP10R")
      (footprint "TP10R")
      (description "Testpoint, Round 1.0mm Dia")
      (fields (field (name "ADDED BY") "Jeremy D") (field (name "CHECKED BY") "Paul B"))
      (libsource (lib "LEGACY_Rigado_AltiumLib") (part "TP_R"))
    )
    (comp (ref "TP107")
      (value "TP10R")
      (footprint "TP10R")
      (description "Testpoint, Round 1.0mm Dia")
      (fields (field (name "ADDED BY") "Jeremy D") (field (name "CHECKED BY") "Paul B"))
      (libsource (lib "LEGACY_Rigado_AltiumLib") (part "TP_R"))
    )
    (comp (ref "TP108")
      (value "TP10R")
      (footprint "TP10R")
      (description "Testpoint, Round 1.0mm Dia")
      (fields (field (name "ADDED BY") "Jeremy D") (field (name "CHECKED BY") "Paul B"))
      (libsource (lib "LEGACY_Rigado_AltiumLib") (part "TP_R"))
    )
    (comp (ref "TP109")
      (value "TP10R")
      (footprint "TP10R")
      (description "Testpoint, Round 1.0mm Dia")
      (fields (field (name "ADDED BY") "Jeremy D") (field (name "CHECKED BY") "Paul B"))
      (libsource (lib "LEGACY_Rigado_AltiumLib") (part "TP_R"))
    )
    (comp (ref "TP110")
      (value "TP10R")
      (footprint "TP10R")
      (description "Testpoint, Round 1.0mm Dia")
      (fields (field (name "ADDED BY") "Jeremy D") (field (name "CHECKED BY") "Paul B"))
      (libsource (lib "LEGACY_Rigado_AltiumLib") (part "TP_R"))
    )
    (comp (ref "TP111")
      (value "TP10R")
      (footprint "TP10R")
      (description "Testpoint, Round 1.0mm Dia")
      (fields (field (name "ADDED BY") "Jeremy D") (field (name "CHECKED BY") "Paul B"))
      (libsource (lib "LEGACY_Rigado_AltiumLib") (part "TP_R"))
    )
    (comp (ref "TP112")
      (value "TP10R")
      (footprint "TP10R")
      (description "Testpoint, Round 1.0mm Dia")
      (fields (field (name "ADDED BY") "Jeremy D") (field (name "CHECKED BY") "Paul B"))
      (libsource (lib "LEGACY_Rigado_AltiumLib") (part "TP_R"))
    )
    (comp (ref "TP113")
      (value "TP10R")
      (footprint "TP10R")
      (description "Testpoint, Round 1.0mm Dia")
      (fields (field (name "ADDED BY") "Jeremy D") (field (name "CHECKED BY") "Paul B"))
      (libsource (lib "LEGACY_Rigado_AltiumLib") (part "TP_R"))
    )
    (comp (ref "TP114")
      (value "TP10R")
      (footprint "TP10R")
      (description "Testpoint, Round 1.0mm Dia")
      (fields (field (name "ADDED BY") "Jeremy D") (field (name "CHECKED BY") "Paul B"))
      (libsource (lib "") (part "TP_R_1"))
    )
    (comp (ref "TP115")
      (value "TP10R")
      (footprint "TP10R")
      (description "Testpoint, Round 1.0mm Dia")
      (fields (field (name "ADDED BY") "Jeremy D") (field (name "CHECKED BY") "Paul B"))
      (libsource (lib "LEGACY_Rigado_AltiumLib") (part "TP_R"))
    )
    (comp (ref "TP116")
      (value "TP10R")
      (footprint "TP10R")
      (description "Testpoint, Round 1.0mm Dia")
      (fields (field (name "ADDED BY") "Jeremy D") (field (name "CHECKED BY") "Paul B"))
      (libsource (lib "LEGACY_Rigado_AltiumLib") (part "TP_R"))
    )
    (comp (ref "TP117")
      (value "TP10R")
      (footprint "TP10R")
      (description "Testpoint, Round 1.0mm Dia")
      (fields (field (name "ADDED BY") "Jeremy D") (field (name "CHECKED BY") "Paul B"))
      (libsource (lib "LEGACY_Rigado_AltiumLib") (part "TP_R"))
    )
    (comp (ref "TP118")
      (value "TP10R")
      (footprint "TP10R")
      (description "Testpoint, Round 1.0mm Dia")
      (fields (field (name "ADDED BY") "Jeremy D") (field (name "CHECKED BY") "Paul B"))
      (libsource (lib "LEGACY_Rigado_AltiumLib") (part "TP_R"))
    )
    (comp (ref "TP119")
      (value "TP10R")
      (footprint "TP10R")
      (description "Testpoint, Round 1.0mm Dia")
      (fields (field (name "ADDED BY") "Jeremy D") (field (name "CHECKED BY") "Paul B"))
      (libsource (lib "LEGACY_Rigado_AltiumLib") (part "TP_R"))
    )
    (comp (ref "TP120")
      (value "TP10R")
      (footprint "TP10R")
      (description "Testpoint, Round 1.0mm Dia")
      (fields (field (name "ADDED BY") "Jeremy D") (field (name "CHECKED BY") "Paul B"))
      (libsource (lib "LEGACY_Rigado_AltiumLib") (part "TP_R"))
    )
    (comp (ref "TP121")
      (value "TP10R")
      (footprint "TP10R")
      (description "Testpoint, Round 1.0mm Dia")
      (fields (field (name "ADDED BY") "Jeremy D") (field (name "CHECKED BY") "Paul B"))
      (libsource (lib "LEGACY_Rigado_AltiumLib") (part "TP_R"))
    )
    (comp (ref "TP122")
      (value "TP10R")
      (footprint "TP10R")
      (description "Testpoint, Round 1.0mm Dia")
      (fields (field (name "ADDED BY") "Jeremy D") (field (name "CHECKED BY") "Paul B"))
      (libsource (lib "LEGACY_Rigado_AltiumLib") (part "TP_R"))
    )
    (comp (ref "TP123")
      (value "TP10R")
      (footprint "TP10R")
      (description "Testpoint, Round 1.0mm Dia")
      (fields (field (name "ADDED BY") "Jeremy D") (field (name "CHECKED BY") "Paul B"))
      (libsource (lib "LEGACY_Rigado_AltiumLib") (part "TP_R"))
    )
    (comp (ref "TP124")
      (value "TP10R")
      (footprint "TP10R")
      (description "Testpoint, Round 1.0mm Dia")
      (fields (field (name "ADDED BY") "Jeremy D") (field (name "CHECKED BY") "Paul B"))
      (libsource (lib "LEGACY_Rigado_AltiumLib") (part "TP_R"))
    )
    (comp (ref "TP125")
      (value "TP10R")
      (footprint "TP10R")
      (description "Testpoint, Round 1.0mm Dia")
      (fields (field (name "ADDED BY") "Jeremy D") (field (name "CHECKED BY") "Paul B"))
      (libsource (lib "") (part "TP_R_1"))
    )
    (comp (ref "TP126")
      (value "TP10R")
      (footprint "TP10R")
      (description "Testpoint, Round 1.0mm Dia")
      (fields (field (name "ADDED BY") "Jeremy D") (field (name "CHECKED BY") "Paul B"))
      (libsource (lib "LEGACY_Rigado_AltiumLib") (part "TP_R"))
    )
    (comp (ref "U5")
      (value "UBXH06-0000120")
      (footprint "SOP65P400X110-8N")
      (description "Non-inverting Buffers & Line Drivers 3 Channels /SOT505/TSSOP8 1.65V to 5.5V")
      (fields
        (field (name "MANUFACTURER_PART_NUMBER") "74LVC3G07DP,125")
        (field (name "MOUSER PART NUMBER") "771-74LVC3G07DP-G")
        (field (name "ARROW PART NUMBER") "74LVC3G07DP,125")
        (field (name "OWNER") "Hozaifa Abdelgadir")
      )
      (libsource (lib "UBX_Arena") (part "74LVC3G07DP,125"))
    )
    (comp (ref "U6")
      (value "UBXH06-0000120")
      (footprint "SOP65P400X110-8N")
      (description "Non-inverting Buffers & Line Drivers 3 Channels /SOT505/TSSOP8 1.65V to 5.5V")
      (fields
        (field (name "MANUFACTURER_PART_NUMBER") "74LVC3G07DP,125")
        (field (name "MOUSER PART NUMBER") "771-74LVC3G07DP-G")
        (field (name "ARROW PART NUMBER") "74LVC3G07DP,125")
        (field (name "OWNER") "Hozaifa Abdelgadir")
      )
      (libsource (lib "UBX_Arena") (part "74LVC3G07DP,125"))
    )
    (comp (ref "U7")
      (value "UBXH06-0000120")
      (footprint "SOP65P400X110-8N")
      (description "Non-inverting Buffers & Line Drivers 3 Channels /SOT505/TSSOP8 1.65V to 5.5V")
      (fields
        (field (name "MANUFACTURER_PART_NUMBER") "74LVC3G07DP,125")
        (field (name "MOUSER PART NUMBER") "771-74LVC3G07DP-G")
        (field (name "ARROW PART NUMBER") "74LVC3G07DP,125")
        (field (name "OWNER") "Hozaifa Abdelgadir")
      )
      (libsource (lib "UBX_Arena") (part "74LVC3G07DP,125"))
    )
  )
  (nets
    (net (code "15") (name "+3V3") (class "Default")
      (node (ref "D10") (pin "2") (pinfunction "A_2") (pintype "passive"))
      (node (ref "D11") (pin "2") (pinfunction "A_2") (pintype "passive"))
      (node (ref "D12") (pin "2") (pinfunction "A_2") (pintype "passive"))
      (node (ref "D13") (pin "2") (pinfunction "A_2") (pintype "passive"))
      (node (ref "D14") (pin "2") (pinfunction "A_2") (pintype "passive"))
      (node (ref "D19") (pin "2") (pinfunction "A_2") (pintype "passive"))
      (node (ref "D9") (pin "2") (pinfunction "A_2") (pintype "passive"))
      (node (ref "J7") (pin "19") (pinfunction "19_19") (pintype "passive"))
      (node (ref "J8") (pin "26") (pinfunction "26_26") (pintype "passive"))
      (node (ref "RGB1") (pin "4") (pinfunction "A_4") (pintype "passive"))
      (node (ref "TP110") (pin "1") (pintype "passive"))
      (node (ref "TP63") (pin "1") (pintype "passive"))
    )
    (net (code "16") (name "+5V") (class "Default")
      (node (ref "J7") (pin "33") (pinfunction "33_33") (pintype "passive"))
      (node (ref "TP77") (pin "1") (pintype "passive"))
    )
    (net (code "17") (name "+Vin") (class "Default")
      (node (ref "J7") (pin "35") (pinfunction "35_35") (pintype "passive"))
      (node (ref "TP79") (pin "1") (pintype "passive"))
    )
    (net (code "18") (name "/Button1") (class "Default")
      (node (ref "J7") (pin "40") (pinfunction "40_40") (pintype "passive"))
      (node (ref "TP84") (pin "1") (pintype "passive"))
    )
    (net (code "19") (name "/Button2") (class "Default")
      (node (ref "J7") (pin "38") (pinfunction "38_38") (pintype "passive"))
      (node (ref "TP82") (pin "1") (pintype "passive"))
    )
    (net (code "20") (name "/Button3") (class "Default")
      (node (ref "J7") (pin "29") (pinfunction "29_29") (pintype "passive"))
      (node (ref "TP72") (pin "1") (pintype "passive"))
    )
    (net (code "21") (name "/Button4") (class "Default")
      (node (ref "J7") (pin "27") (pinfunction "27_27") (pintype "passive"))
      (node (ref "TP71") (pin "1") (pintype "passive"))
    )
    (net (code "22") (name "/CTS") (class "Default")
      (node (ref "R64") (pin "1") (pinfunction "1_1") (pintype "passive"))
      (node (ref "U5") (pin "5") (pinfunction "2Y_5") (pintype "passive"))
    )
    (net (code "23") (name "/DSR") (class "Default")
      (node (ref "R59") (pin "1") (pinfunction "1_1") (pintype "passive"))
      (node (ref "U5") (pin "7") (pinfunction "1Y_7") (pintype "passive"))
    )
    (net (code "24") (name "/DTR") (class "Default")
      (node (ref "R61") (pin "1") (pinfunction "1_1") (pintype "passive"))
      (node (ref "U5") (pin "2") (pinfunction "3Y_2") (pintype "passive"))
    )
    (net (code "25") (name "/GREEN") (class "Default")
      (node (ref "R72") (pin "1") (pinfunction "1_1") (pintype "passive"))
      (node (ref "U7") (pin "2") (pinfunction "3Y_2") (pintype "passive"))
    )
    (net (code "26") (name "/P0.00{slash}D_TX") (class "Default")
      (node (ref "J7") (pin "36") (pinfunction "36_36") (pintype "passive"))
      (node (ref "TP80") (pin "1") (pintype "passive"))
    )
    (net (code "27") (name "/P0.01{slash}D_RX") (class "Default")
      (node (ref "J7") (pin "34") (pinfunction "34_34") (pintype "passive"))
      (node (ref "TP78") (pin "1") (pintype "passive"))
    )
    (net (code "28") (name "/P0.02{slash}I2C_SDA") (class "Default")
      (node (ref "J7") (pin "17") (pinfunction "17_17") (pintype "passive"))
      (node (ref "TP61") (pin "1") (pintype "passive"))
    )
    (net (code "29") (name "/P0.03{slash}I2C_SCL") (class "Default")
      (node (ref "J7") (pin "15") (pinfunction "15_15") (pintype "passive"))
      (node (ref "TP59") (pin "1") (pintype "passive"))
    )
    (net (code "30") (name "/P0.04{slash}LED_GREEN{slash}SW1") (class "Default")
      (node (ref "J7") (pin "30") (pinfunction "30_30") (pintype "passive"))
      (node (ref "R76") (pin "2") (pinfunction "2_2") (pintype "passive"))
      (node (ref "TP73") (pin "1") (pintype "passive"))
    )
    (net (code "31") (name "/P1.00{slash}XL1") (class "Default")
      (node (ref "J8") (pin "3") (pinfunction "3_3") (pintype "passive"))
      (node (ref "TP86") (pin "1") (pintype "passive"))
    )
    (net (code "32") (name "/P1.01{slash}XL2") (class "Default")
      (node (ref "J8") (pin "5") (pinfunction "5_5") (pintype "passive"))
      (node (ref "TP89") (pin "1") (pintype "passive"))
    )
    (net (code "33") (name "/P1.02") (class "Default")
      (node (ref "J8") (pin "7") (pinfunction "7_7") (pintype "passive"))
      (node (ref "TP91") (pin "1") (pintype "passive"))
    )
    (net (code "34") (name "/P1.03") (class "Default")
      (node (ref "J8") (pin "9") (pinfunction "9_9") (pintype "passive"))
      (node (ref "TP93") (pin "1") (pintype "passive"))
    )
    (net (code "35") (name "/P1.04{slash}UART1_TX") (class "Default")
      (node (ref "J7") (pin "16") (pinfunction "16_16") (pintype "passive"))
      (node (ref "TP60") (pin "1") (pintype "passive"))
    )
    (net (code "36") (name "/P1.05{slash}UART1_RX") (class "Default")
      (node (ref "J7") (pin "18") (pinfunction "18_18") (pintype "passive"))
      (node (ref "TP62") (pin "1") (pintype "passive"))
    )
    (net (code "37") (name "/P1.06{slash}UART1_RTS") (class "Default")
      (node (ref "J7") (pin "20") (pinfunction "20_20") (pintype "passive"))
      (node (ref "TP64") (pin "1") (pintype "passive"))
    )
    (net (code "38") (name "/P1.07{slash}UART1_CTS") (class "Default")
      (node (ref "J7") (pin "22") (pinfunction "22_22") (pintype "passive"))
      (node (ref "TP65") (pin "1") (pintype "passive"))
    )
    (net (code "39") (name "/P1.08{slash}EXTREF{slash}SW3") (class "Default")
      (node (ref "J8") (pin "11") (pinfunction "11_11") (pintype "passive"))
      (node (ref "TP94") (pin "1") (pintype "passive"))
    )
    (net (code "40") (name "/P1.09{slash}LED_BLUE") (class "Default")
      (node (ref "J8") (pin "2") (pinfunction "2_2") (pintype "passive"))
      (node (ref "R73") (pin "2") (pinfunction "2_2") (pintype "passive"))
      (node (ref "TP85") (pin "1") (pintype "passive"))
    )
    (net (code "41") (name "/P1.10{slash}SW2") (class "Default")
      (node (ref "J7") (pin "32") (pinfunction "32_32") (pintype "passive"))
      (node (ref "TP76") (pin "1") (pintype "passive"))
    )
    (net (code "42") (name "/P1.11") (class "Default")
      (node (ref "J8") (pin "4") (pinfunction "4_4") (pintype "passive"))
      (node (ref "TP87") (pin "1") (pintype "passive"))
    )
    (net (code "43") (name "/P1.12") (class "Default")
      (node (ref "J8") (pin "6") (pinfunction "6_6") (pintype "passive"))
      (node (ref "TP90") (pin "1") (pintype "passive"))
    )
    (net (code "44") (name "/P1.13{slash}WAKE_UP") (class "Default")
      (node (ref "J7") (pin "26") (pinfunction "26_26") (pintype "passive"))
      (node (ref "TP70") (pin "1") (pintype "passive"))
    )
    (net (code "45") (name "/P1.14{slash}WAKE-HOST") (class "Default")
      (node (ref "J7") (pin "24") (pinfunction "24_24") (pintype "passive"))
      (node (ref "TP67") (pin "1") (pintype "passive"))
    )
    (net (code "46") (name "/P1.15{slash}LED_RED{slash}SW4") (class "Default")
      (node (ref "J8") (pin "8") (pinfunction "8_8") (pintype "passive"))
      (node (ref "R70") (pin "2") (pinfunction "2_2") (pintype "passive"))
      (node (ref "TP92") (pin "1") (pintype "passive"))
    )
    (net (code "47") (name "/P2.00") (class "Default")
      (node (ref "J7") (pin "3") (pinfunction "3_3") (pintype "passive"))
      (node (ref "TP46") (pin "1") (pintype "passive"))
    )
    (net (code "48") (name "/P2.01") (class "Default")
      (node (ref "J7") (pin "4") (pinfunction "4_4") (pintype "passive"))
      (node (ref "TP47") (pin "1") (pintype "passive"))
    )
    (net (code "49") (name "/P2.02") (class "Default")
      (node (ref "J7") (pin "5") (pinfunction "5_5") (pintype "passive"))
      (node (ref "TP49") (pin "1") (pintype "passive"))
    )
    (net (code "50") (name "/P2.03") (class "Default")
      (node (ref "J7") (pin "6") (pinfunction "6_6") (pintype "passive"))
      (node (ref "TP50") (pin "1") (pintype "passive"))
    )
    (net (code "51") (name "/P2.04") (class "Default")
      (node (ref "J7") (pin "7") (pinfunction "7_7") (pintype "passive"))
      (node (ref "TP51") (pin "1") (pintype "passive"))
    )
    (net (code "52") (name "/P2.05") (class "Default")
      (node (ref "J7") (pin "8") (pinfunction "8_8") (pintype "passive"))
      (node (ref "TP52") (pin "1") (pintype "passive"))
    )
    (net (code "53") (name "/P2.06{slash}SPI_CLK{slash}TRACE_CLK") (class "Default")
      (node (ref "J7") (pin "9") (pinfunction "9_9") (pintype "passive"))
      (node (ref "TP53") (pin "1") (pintype "passive"))
    )
    (net (code "54") (name "/P2.07{slash}SPI_DCX{slash}TRACE_D0{slash}SWO") (class "Default")
      (node (ref "J7") (pin "12") (pinfunction "12_12") (pintype "passive"))
      (node (ref "R74") (pin "2") (pinfunction "2_2") (pintype "passive"))
      (node (ref "TP55") (pin "1") (pintype "passive"))
    )
    (net (code "55") (name "/P2.08{slash}SPI_MOSI{slash}TRACE_D1") (class "Default")
      (node (ref "J7") (pin "11") (pinfunction "11_11") (pintype "passive"))
      (node (ref "TP54") (pin "1") (pintype "passive"))
    )
    (net (code "56") (name "/P2.09{slash}SPI_MISO{slash}TRACE_D2") (class "Default")
      (node (ref "J7") (pin "14") (pinfunction "14_14") (pintype "passive"))
      (node (ref "R69") (pin "2") (pinfunction "2_2") (pintype "passive"))
      (node (ref "TP58") (pin "1") (pintype "passive"))
    )
    (net (code "57") (name "/P2.10{slash}SPI_CS{slash}TRACE_D3") (class "Default")
      (node (ref "J7") (pin "13") (pinfunction "13_13") (pintype "passive"))
      (node (ref "TP57") (pin "1") (pintype "passive"))
    )
    (net (code "58") (name "/RTS") (class "Default")
      (node (ref "R66") (pin "1") (pinfunction "1_1") (pintype "passive"))
      (node (ref "U6") (pin "7") (pinfunction "1Y_7") (pintype "passive"))
    )
    (net (code "59") (name "/RXD") (class "Default")
      (node (ref "R67") (pin "1") (pinfunction "1_1") (pintype "passive"))
      (node (ref "U6") (pin "2") (pinfunction "3Y_2") (pintype "passive"))
    )
    (net (code "60") (name "/SWDCLK_ANNA") (class "Default")
      (node (ref "J8") (pin "22") (pinfunction "22_22") (pintype "passive"))
      (node (ref "TP105") (pin "1") (pintype "passive"))
    )
    (net (code "61") (name "/SWDIO_ANNA") (class "Default")
      (node (ref "J8") (pin "24") (pinfunction "24_24") (pintype "passive"))
      (node (ref "TP107") (pin "1") (pintype "passive"))
    )
    (net (code "62") (name "/TXD") (class "Default")
      (node (ref "R68") (pin "1") (pinfunction "1_1") (pintype "passive"))
      (node (ref "U6") (pin "5") (pinfunction "2Y_5") (pintype "passive"))
    )
    (net (code "63") (name "/UART0_OBD-CTS") (class "Default")
      (node (ref "J7") (pin "31") (pinfunction "31_31") (pintype "passive"))
      (node (ref "TP75") (pin "1") (pintype "passive"))
    )
    (net (code "64") (name "/UART0_OBD-RTS") (class "Default")
      (node (ref "J7") (pin "25") (pinfunction "25_25") (pintype "passive"))
      (node (ref "TP69") (pin "1") (pintype "passive"))
    )
    (net (code "65") (name "/UART1-CTS") (class "Default")
      (node (ref "R60") (pin "2") (pinfunction "2_2") (pintype "passive"))
    )
    (net (code "66") (name "/UART1-DSR") (class "Default")
      (node (ref "R57") (pin "2") (pinfunction "2_2") (pintype "passive"))
    )
    (net (code "67") (name "/UART1-DTR") (class "Default")
      (node (ref "R58") (pin "2") (pinfunction "2_2") (pintype "passive"))
    )
    (net (code "68") (name "/UART1-RTS") (class "Default")
      (node (ref "R62") (pin "2") (pinfunction "2_2") (pintype "passive"))
    )
    (net (code "69") (name "/UART1-RXD") (class "Default")
      (node (ref "R63") (pin "2") (pinfunction "2_2") (pintype "passive"))
    )
    (net (code "70") (name "/UART1-TXD") (class "Default")
      (node (ref "R65") (pin "2") (pinfunction "2_2") (pintype "passive"))
    )
    (net (code "71") (name "/UART1_OBD-CTS") (class "Default")
      (node (ref "J8") (pin "34") (pinfunction "34_34") (pintype "passive"))
      (node (ref "TP118") (pin "1") (pintype "passive"))
    )
    (net (code "72") (name "/UART1_OBD-RTS") (class "Default")
      (node (ref "J8") (pin "36") (pinfunction "36_36") (pintype "passive"))
      (node (ref "TP120") (pin "1") (pintype "passive"))
    )
    (net (code "73") (name "/UART1_OBD-RXD") (class "Default")
      (node (ref "J8") (pin "30") (pinfunction "30_30") (pintype "passive"))
      (node (ref "TP113") (pin "1") (pintype "passive"))
    )
    (net (code "74") (name "/UART1_OBD-TXD") (class "Default")
      (node (ref "J8") (pin "32") (pinfunction "32_32") (pintype "passive"))
      (node (ref "TP116") (pin "1") (pintype "passive"))
    )
    (net (code "75") (name "/nRESET") (class "Default")
      (node (ref "J8") (pin "20") (pinfunction "20_20") (pintype "passive"))
      (node (ref "TP104") (pin "1") (pintype "passive"))
    )
    (net (code "90") (name "GND") (class "Default")
      (node (ref "J7") (pin "1") (pinfunction "1_1") (pintype "passive"))
      (node (ref "J7") (pin "10") (pinfunction "10_10") (pintype "passive"))
      (node (ref "J7") (pin "21") (pinfunction "21_21") (pintype "passive"))
      (node (ref "J7") (pin "28") (pinfunction "28_28") (pintype "passive"))
      (node (ref "J8") (pin "1") (pinfunction "1_1") (pintype "passive"))
      (node (ref "J8") (pin "10") (pinfunction "10_10") (pintype "passive"))
      (node (ref "J8") (pin "21") (pinfunction "21_21") (pintype "passive"))
      (node (ref "J8") (pin "28") (pinfunction "28_28") (pintype "passive"))
      (node (ref "R77") (pin "1") (pinfunction "1_1") (pintype "passive"))
      (node (ref "TP108") (pin "1") (pintype "passive"))
      (node (ref "TP114") (pin "1") (pintype "passive"))
      (node (ref "TP38") (pin "1") (pintype "passive"))
      (node (ref "TP44") (pin "1") (pintype "passive"))
      (node (ref "TP48") (pin "1") (pintype "passive"))
      (node (ref "TP56") (pin "1") (pintype "passive"))
      (node (ref "TP68") (pin "1") (pintype "passive"))
      (node (ref "TP74") (pin "1") (pintype "passive"))
      (node (ref "TP88") (pin "1") (pintype "passive"))
      (node (ref "TP96") (pin "1") (pintype "passive"))
      (node (ref "U5") (pin "4") (pinfunction "GND_4") (pintype "passive"))
      (node (ref "U6") (pin "4") (pinfunction "GND_4") (pintype "passive"))
      (node (ref "U7") (pin "4") (pinfunction "GND_4") (pintype "passive"))
    )
    (net (code "91") (name "Net-(D9-C)") (class "Default")
      (node (ref "D9") (pin "1") (pinfunction "C_1") (pintype "passive"))
      (node (ref "R59") (pin "2") (pinfunction "2_2") (pintype "passive"))
    )
    (net (code "92") (name "Net-(D10-C)") (class "Default")
      (node (ref "D10") (pin "1") (pinfunction "C_1") (pintype "passive"))
      (node (ref "R61") (pin "2") (pinfunction "2_2") (pintype "passive"))
    )
    (net (code "93") (name "Net-(D11-C)") (class "Default")
      (node (ref "D11") (pin "1") (pinfunction "C_1") (pintype "passive"))
      (node (ref "R64") (pin "2") (pinfunction "2_2") (pintype "passive"))
    )
    (net (code "94") (name "Net-(D12-C)") (class "Default")
      (node (ref "D12") (pin "1") (pinfunction "C_1") (pintype "passive"))
      (node (ref "R66") (pin "2") (pinfunction "2_2") (pintype "passive"))
    )
    (net (code "95") (name "Net-(D13-C)") (class "Default")
      (node (ref "D13") (pin "1") (pinfunction "C_1") (pintype "passive"))
      (node (ref "R67") (pin "2") (pinfunction "2_2") (pintype "passive"))
    )
    (net (code "96") (name "Net-(D14-C)") (class "Default")
      (node (ref "D14") (pin "1") (pinfunction "C_1") (pintype "passive"))
      (node (ref "R68") (pin "2") (pinfunction "2_2") (pintype "passive"))
    )
    (net (code "97") (name "Net-(D19-C)") (class "Default")
      (node (ref "D19") (pin "1") (pinfunction "C_1") (pintype "passive"))
      (node (ref "R77") (pin "2") (pinfunction "2_2") (pintype "passive"))
    )
    (net (code "98") (name "Net-(J7-Pad2)") (class "Default")
      (node (ref "J7") (pin "2") (pinfunction "2_2") (pintype "passive"))
      (node (ref "TP45") (pin "1") (pintype "passive"))
    )
    (net (code "99") (name "Net-(J7-Pad23)") (class "Default")
      (node (ref "J7") (pin "23") (pinfunction "23_23") (pintype "passive"))
      (node (ref "TP66") (pin "1") (pintype "passive"))
    )
    (net (code "100") (name "Net-(J8-Pad12)") (class "Default")
      (node (ref "J8") (pin "12") (pinfunction "12_12") (pintype "passive"))
      (node (ref "TP95") (pin "1") (pintype "passive"))
    )
    (net (code "101") (name "Net-(J8-Pad13)") (class "Default")
      (node (ref "J8") (pin "13") (pinfunction "13_13") (pintype "passive"))
      (node (ref "TP97") (pin "1") (pintype "passive"))
    )
    (net (code "102") (name "Net-(J8-Pad14)") (class "Default")
      (node (ref "J8") (pin "14") (pinfunction "14_14") (pintype "passive"))
      (node (ref "TP98") (pin "1") (pintype "passive"))
    )
    (net (code "103") (name "Net-(J8-Pad15)") (class "Default")
      (node (ref "J8") (pin "15") (pinfunction "15_15") (pintype "passive"))
      (node (ref "TP99") (pin "1") (pintype "passive"))
    )
    (net (code "104") (name "Net-(J8-Pad16)") (class "Default")
      (node (ref "J8") (pin "16") (pinfunction "16_16") (pintype "passive"))
      (node (ref "TP100") (pin "1") (pintype "passive"))
    )
    (net (code "105") (name "Net-(J8-Pad17)") (class "Default")
      (node (ref "J8") (pin "17") (pinfunction "17_17") (pintype "passive"))
      (node (ref "TP101") (pin "1") (pintype "passive"))
    )
    (net (code "106") (name "Net-(J8-Pad18)") (class "Default")
      (node (ref "J8") (pin "18") (pinfunction "18_18") (pintype "passive"))
      (node (ref "TP102") (pin "1") (pintype "passive"))
    )
    (net (code "107") (name "Net-(J8-Pad19)") (class "Default")
      (node (ref "J8") (pin "19") (pinfunction "19_19") (pintype "passive"))
      (node (ref "TP103") (pin "1") (pintype "passive"))
    )
    (net (code "108") (name "Net-(J8-Pad23)") (class "Default")
      (node (ref "J8") (pin "23") (pinfunction "23_23") (pintype "passive"))
      (node (ref "TP106") (pin "1") (pintype "passive"))
    )
    (net (code "109") (name "Net-(J8-Pad25)") (class "Default")
      (node (ref "J8") (pin "25") (pinfunction "25_25") (pintype "passive"))
      (node (ref "TP109") (pin "1") (pintype "passive"))
    )
    (net (code "110") (name "Net-(J8-Pad27)") (class "Default")
      (node (ref "J8") (pin "27") (pinfunction "27_27") (pintype "passive"))
      (node (ref "TP111") (pin "1") (pintype "passive"))
    )
    (net (code "111") (name "Net-(J8-Pad29)") (class "Default")
      (node (ref "J8") (pin "29") (pinfunction "29_29") (pintype "passive"))
      (node (ref "TP112") (pin "1") (pintype "passive"))
    )
    (net (code "112") (name "Net-(J8-Pad31)") (class "Default")
      (node (ref "J8") (pin "31") (pinfunction "31_31") (pintype "passive"))
      (node (ref "TP115") (pin "1") (pintype "passive"))
    )
    (net (code "113") (name "Net-(J8-Pad33)") (class "Default")
      (node (ref "J8") (pin "33") (pinfunction "33_33") (pintype "passive"))
      (node (ref "TP117") (pin "1") (pintype "passive"))
    )
    (net (code "114") (name "Net-(J8-Pad35)") (class "Default")
      (node (ref "J8") (pin "35") (pinfunction "35_35") (pintype "passive"))
      (node (ref "TP119") (pin "1") (pintype "passive"))
    )
    (net (code "115") (name "Net-(J8-Pad37)") (class "Default")
      (node (ref "J8") (pin "37") (pinfunction "37_37") (pintype "passive"))
      (node (ref "TP121") (pin "1") (pintype "passive"))
    )
    (net (code "116") (name "Net-(J8-Pad38)") (class "Default")
      (node (ref "J8") (pin "38") (pinfunction "38_38") (pintype "passive"))
      (node (ref "TP122") (pin "1") (pintype "passive"))
    )
    (net (code "117") (name "Net-(J8-Pad39)") (class "Default")
      (node (ref "J8") (pin "39") (pinfunction "39_39") (pintype "passive"))
      (node (ref "TP123") (pin "1") (pintype "passive"))
    )
    (net (code "118") (name "Net-(J8-Pad40)") (class "Default")
      (node (ref "J8") (pin "40") (pinfunction "40_40") (pintype "passive"))
      (node (ref "TP124") (pin "1") (pintype "passive"))
    )
    (net (code "119") (name "Net-(RGB1-B)") (class "Default")
      (node (ref "R75") (pin "2") (pinfunction "2_2") (pintype "passive"))
      (node (ref "RGB1") (pin "3") (pinfunction "B_3") (pintype "passive"))
    )
    (net (code "120") (name "Net-(RGB1-G)") (class "Default")
      (node (ref "R72") (pin "2") (pinfunction "2_2") (pintype "passive"))
      (node (ref "RGB1") (pin "2") (pinfunction "G_2") (pintype "passive"))
    )
    (net (code "121") (name "Net-(RGB1-R)") (class "Default")
      (node (ref "R71") (pin "2") (pinfunction "2_2") (pintype "passive"))
      (node (ref "RGB1") (pin "1") (pinfunction "R_1") (pintype "passive"))
    )
    (net (code "122") (name "Net-(U5-1A)") (class "Default")
      (node (ref "R57") (pin "1") (pinfunction "1_1") (pintype "passive"))
      (node (ref "U5") (pin "1") (pinfunction "1A_1") (pintype "passive"))
    )
    (net (code "123") (name "Net-(U5-2A)") (class "Default")
      (node (ref "R60") (pin "1") (pinfunction "1_1") (pintype "passive"))
      (node (ref "U5") (pin "3") (pinfunction "2A_3") (pintype "passive"))
    )
    (net (code "124") (name "Net-(U5-3A)") (class "Default")
      (node (ref "R58") (pin "1") (pinfunction "1_1") (pintype "passive"))
      (node (ref "U5") (pin "6") (pinfunction "3A_6") (pintype "passive"))
    )
    (net (code "125") (name "Net-(U6-1A)") (class "Default")
      (node (ref "R62") (pin "1") (pinfunction "1_1") (pintype "passive"))
      (node (ref "U6") (pin "1") (pinfunction "1A_1") (pintype "passive"))
    )
    (net (code "126") (name "Net-(U6-2A)") (class "Default")
      (node (ref "R65") (pin "1") (pinfunction "1_1") (pintype "passive"))
      (node (ref "U6") (pin "3") (pinfunction "2A_3") (pintype "passive"))
    )
    (net (code "127") (name "Net-(U6-3A)") (class "Default")
      (node (ref "R63") (pin "1") (pinfunction "1_1") (pintype "passive"))
      (node (ref "U6") (pin "6") (pinfunction "3A_6") (pintype "passive"))
    )
    (net (code "128") (name "Net-(U7-1A)") (class "Default")
      (node (ref "R222") (pin "2") (pinfunction "2_2") (pintype "passive"))
      (node (ref "R69") (pin "1") (pinfunction "1_1") (pintype "passive"))
      (node (ref "R70") (pin "1") (pinfunction "1_1") (pintype "passive"))
      (node (ref "U7") (pin "1") (pinfunction "1A_1") (pintype "passive"))
    )
    (net (code "129") (name "Net-(U7-1Y)") (class "Default")
      (node (ref "R71") (pin "1") (pinfunction "1_1") (pintype "passive"))
      (node (ref "U7") (pin "7") (pinfunction "1Y_7") (pintype "passive"))
    )
    (net (code "130") (name "Net-(U7-2A)") (class "Default")
      (node (ref "R223") (pin "2") (pinfunction "2_2") (pintype "passive"))
      (node (ref "R73") (pin "1") (pinfunction "1_1") (pintype "passive"))
      (node (ref "U7") (pin "3") (pinfunction "2A_3") (pintype "passive"))
    )
    (net (code "131") (name "Net-(U7-2Y)") (class "Default")
      (node (ref "R75") (pin "1") (pinfunction "1_1") (pintype "passive"))
      (node (ref "U7") (pin "5") (pinfunction "2Y_5") (pintype "passive"))
    )
    (net (code "132") (name "Net-(U7-3A)") (class "Default")
      (node (ref "R224") (pin "2") (pinfunction "2_2") (pintype "passive"))
      (node (ref "R74") (pin "1") (pinfunction "1_1") (pintype "passive"))
      (node (ref "R76") (pin "1") (pinfunction "1_1") (pintype "passive"))
      (node (ref "U7") (pin "6") (pinfunction "3A_6") (pintype "passive"))
    )
    (net (code "133") (name "VBUS") (class "Default")
      (node (ref "J7") (pin "39") (pinfunction "39_39") (pintype "passive"))
      (node (ref "TP83") (pin "1") (pintype "passive"))
    )
    (net (code "134") (name "VDDIO_Periph") (class "Default")
      (node (ref "J7") (pin "37") (pinfunction "37_37") (pintype "passive"))
      (node (ref "R222") (pin "1") (pinfunction "1_1") (pintype "passive"))
      (node (ref "R223") (pin "1") (pinfunction "1_1") (pintype "passive"))
      (node (ref "R224") (pin "1") (pinfunction "1_1") (pintype "passive"))
      (node (ref "TP81") (pin "1") (pintype "passive"))
      (node (ref "U5") (pin "8") (pinfunction "VCC_8") (pintype "passive"))
      (node (ref "U6") (pin "8") (pinfunction "VCC_8") (pintype "passive"))
      (node (ref "U7") (pin "8") (pinfunction "VCC_8") (pintype "passive"))
    )
    (net (code "135") (name "unconnected-(TP2-Pad1)") (class "Default")
      (node (ref "TP2") (pin "1") (pintype "passive+no_connect"))
    )
    (net (code "136") (name "unconnected-(TP3-Pad1)") (class "Default")
      (node (ref "TP3") (pin "1") (pintype "passive+no_connect"))
    )
    (net (code "137") (name "unconnected-(TP6-Pad1)") (class "Default")
      (node (ref "TP6") (pin "1") (pintype "passive+no_connect"))
    )
    (net (code "138") (name "unconnected-(TP7-Pad1)") (class "Default")
      (node (ref "TP7") (pin "1") (pintype "passive+no_connect"))
    )
    (net (code "139") (name "unconnected-(TP8-Pad1)") (class "Default")
      (node (ref "TP8") (pin "1") (pintype "passive+no_connect"))
    )
    (net (code "140") (name "unconnected-(TP9-Pad1)") (class "Default")
      (node (ref "TP9") (pin "1") (pintype "passive+no_connect"))
    )
    (net (code "141") (name "unconnected-(TP10-Pad1)") (class "Default")
      (node (ref "TP10") (pin "1") (pintype "passive+no_connect"))
    )
    (net (code "142") (name "unconnected-(TP11-Pad1)") (class "Default")
      (node (ref "TP11") (pin "1") (pintype "passive+no_connect"))
    )
    (net (code "143") (name "unconnected-(TP12-Pad1)") (class "Default")
      (node (ref "TP12") (pin "1") (pintype "passive+no_connect"))
    )
    (net (code "144") (name "unconnected-(TP13-Pad1)") (class "Default")
      (node (ref "TP13") (pin "1") (pintype "passive+no_connect"))
    )
    (net (code "145") (name "unconnected-(TP14-Pad1)") (class "Default")
      (node (ref "TP14") (pin "1") (pintype "passive+no_connect"))
    )
    (net (code "146") (name "unconnected-(TP15-Pad1)") (class "Default")
      (node (ref "TP15") (pin "1") (pintype "passive+no_connect"))
    )
    (net (code "147") (name "unconnected-(TP18-Pad1)") (class "Default")
      (node (ref "TP18") (pin "1") (pintype "passive+no_connect"))
    )
    (net (code "148") (name "unconnected-(TP19-Pad1)") (class "Default")
      (node (ref "TP19") (pin "1") (pintype "passive+no_connect"))
    )
    (net (code "149") (name "unconnected-(TP20-Pad1)") (class "Default")
      (node (ref "TP20") (pin "1") (pintype "passive+no_connect"))
    )
    (net (code "150") (name "unconnected-(TP21-Pad1)") (class "Default")
      (node (ref "TP21") (pin "1") (pintype "passive+no_connect"))
    )
    (net (code "151") (name "unconnected-(TP22-Pad1)") (class "Default")
      (node (ref "TP22") (pin "1") (pintype "passive+no_connect"))
    )
    (net (code "152") (name "unconnected-(TP23-Pad1)") (class "Default")
      (node (ref "TP23") (pin "1") (pintype "passive+no_connect"))
    )
    (net (code "153") (name "unconnected-(TP24-Pad1)") (class "Default")
      (node (ref "TP24") (pin "1") (pintype "passive+no_connect"))
    )
    (net (code "154") (name "unconnected-(TP25-Pad1)") (class "Default")
      (node (ref "TP25") (pin "1") (pintype "passive+no_connect"))
    )
    (net (code "155") (name "unconnected-(TP32-Pad1)") (class "Default")
      (node (ref "TP32") (pin "1") (pintype "passive+no_connect"))
    )
    (net (code "156") (name "unconnected-(TP33-Pad1)") (class "Default")
      (node (ref "TP33") (pin "1") (pintype "passive+no_connect"))
    )
    (net (code "157") (name "unconnected-(TP34-Pad1)") (class "Default")
      (node (ref "TP34") (pin "1") (pintype "passive+no_connect"))
    )
    (net (code "158") (name "unconnected-(TP35-Pad1)") (class "Default")
      (node (ref "TP35") (pin "1") (pintype "passive+no_connect"))
    )
    (net (code "159") (name "unconnected-(TP39-Pad1)") (class "Default")
      (node (ref "TP39") (pin "1") (pintype "passive+no_connect"))
    )
    (net (code "160") (name "unconnected-(TP40-Pad1)") (class "Default")
      (node (ref "TP40") (pin "1") (pintype "passive+no_connect"))
    )
    (net (code "161") (name "unconnected-(TP41-Pad1)") (class "Default")
      (node (ref "TP41") (pin "1") (pintype "passive+no_connect"))
    )
    (net (code "162") (name "unconnected-(TP125-Pad1)") (class "Default")
      (node (ref "TP125") (pin "1") (pintype "passive+no_connect"))
    )
    (net (code "163") (name "unconnected-(TP126-Pad1)") (class "Default")
      (node (ref "TP126") (pin "1") (pintype "passive+no_connect"))
    )
  )
)
